# MCU.net
KiCad netlist of a schematic drawn in Altium Designer
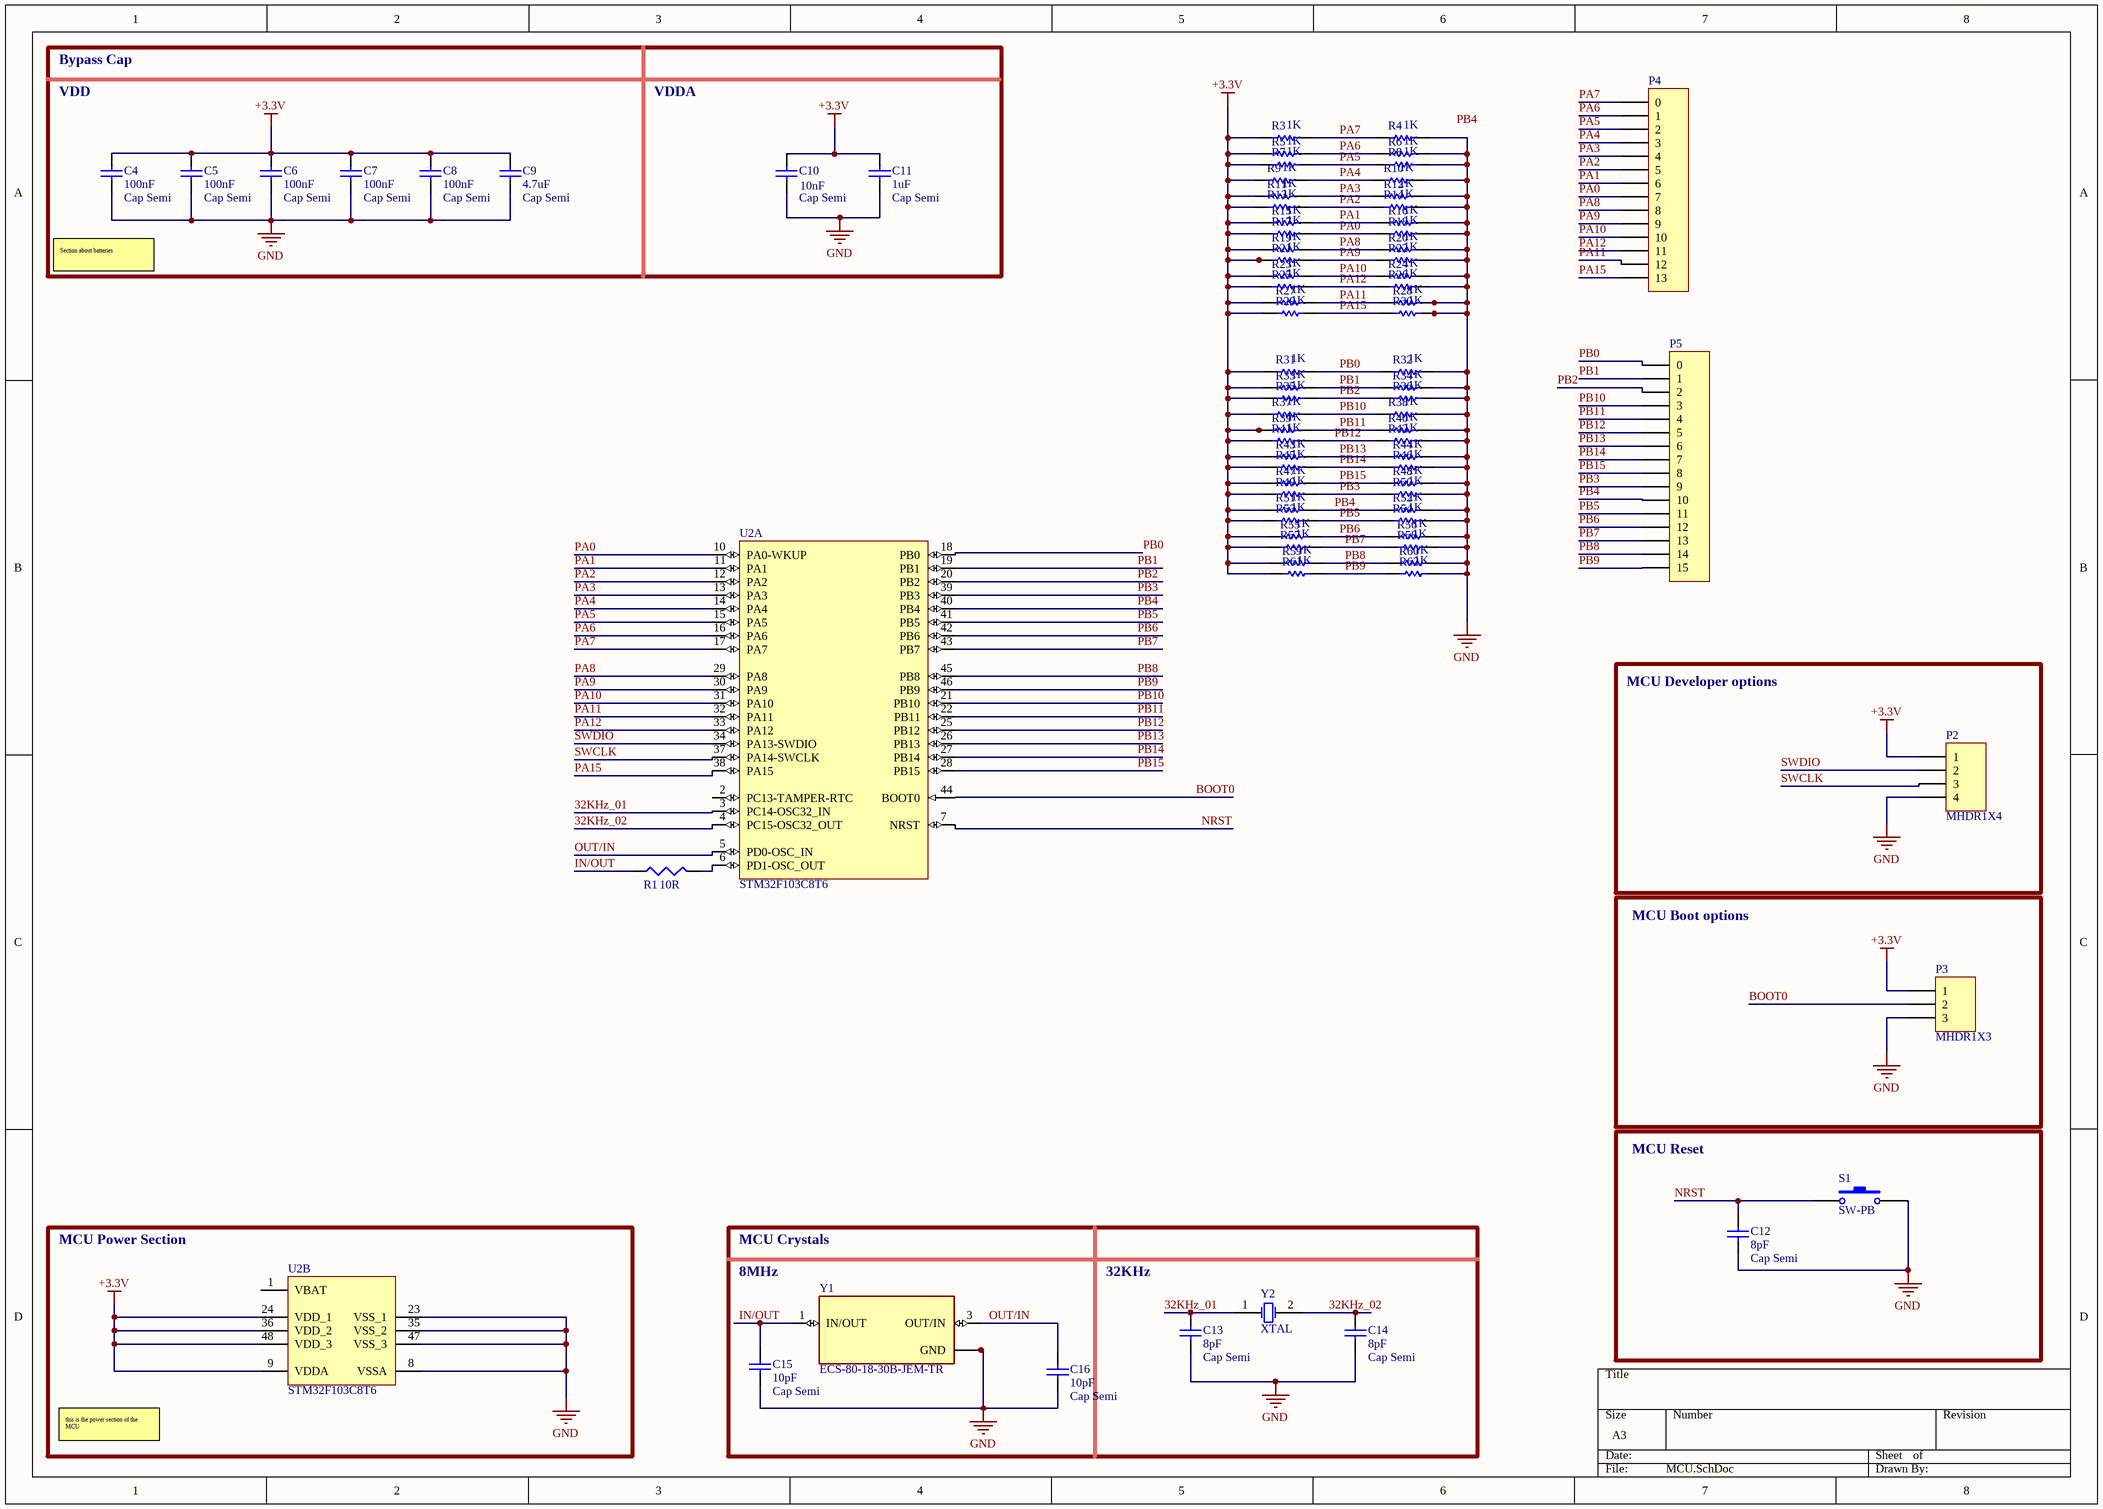
[diagram p0: MCU.SchDoc]

(export (version "E")
  (design (tool "Eeschema 10.0.6"))
  (components
    (comp (ref "C4")
      (value "Cap Semi")
      (footprint "1608[0603]")
      (description "Capacitor (Semiconductor SIM Model)")
      (fields (field (name "ALTIUM_VALUE") "100nF") (field (name "PUBLISHER") "Altium Limited"))
      (libsource (lib "Miscellaneous Devices") (part "Cap Semi"))
    )
    (comp (ref "C5")
      (value "Cap Semi")
      (footprint "1608[0603]")
      (description "Capacitor (Semiconductor SIM Model)")
      (fields (field (name "ALTIUM_VALUE") "100nF") (field (name "PUBLISHER") "Altium Limited"))
      (libsource (lib "Miscellaneous Devices") (part "Cap Semi"))
    )
    (comp (ref "C6")
      (value "Cap Semi")
      (footprint "1608[0603]")
      (description "Capacitor (Semiconductor SIM Model)")
      (fields (field (name "ALTIUM_VALUE") "100nF") (field (name "PUBLISHER") "Altium Limited"))
      (libsource (lib "Miscellaneous Devices") (part "Cap Semi"))
    )
    (comp (ref "C7")
      (value "Cap Semi")
      (footprint "1608[0603]")
      (description "Capacitor (Semiconductor SIM Model)")
      (fields (field (name "ALTIUM_VALUE") "100nF") (field (name "PUBLISHER") "Altium Limited"))
      (libsource (lib "Miscellaneous Devices") (part "Cap Semi"))
    )
    (comp (ref "C8")
      (value "Cap Semi")
      (footprint "1608[0603]")
      (description "Capacitor (Semiconductor SIM Model)")
      (fields (field (name "ALTIUM_VALUE") "100nF") (field (name "PUBLISHER") "Altium Limited"))
      (libsource (lib "Miscellaneous Devices") (part "Cap Semi"))
    )
    (comp (ref "C9")
      (value "Cap Semi")
      (footprint "1608[0603]")
      (description "Capacitor (Semiconductor SIM Model)")
      (fields (field (name "ALTIUM_VALUE") "4.7uF") (field (name "PUBLISHER") "Altium Limited"))
      (libsource (lib "Miscellaneous Devices") (part "Cap Semi"))
    )
    (comp (ref "C10")
      (value "Cap Semi")
      (footprint "1608[0603]")
      (description "Capacitor (Semiconductor SIM Model)")
      (fields (field (name "ALTIUM_VALUE") "10nF") (field (name "PUBLISHER") "Altium Limited"))
      (libsource (lib "Miscellaneous Devices") (part "Cap Semi"))
    )
    (comp (ref "C11")
      (value "Cap Semi")
      (footprint "1608[0603]")
      (description "Capacitor (Semiconductor SIM Model)")
      (fields (field (name "ALTIUM_VALUE") "1uF") (field (name "PUBLISHER") "Altium Limited"))
      (libsource (lib "Miscellaneous Devices") (part "Cap Semi"))
    )
    (comp (ref "C12")
      (value "Cap Semi")
      (footprint "0402")
      (description "Capacitor (Semiconductor SIM Model)")
      (fields (field (name "ALTIUM_VALUE") "8pF") (field (name "PUBLISHER") "Altium Limited"))
      (libsource (lib "Miscellaneous Devices") (part "Cap Semi"))
    )
    (comp (ref "C13")
      (value "Cap Semi")
      (footprint "0402")
      (description "Capacitor (Semiconductor SIM Model)")
      (fields (field (name "ALTIUM_VALUE") "8pF") (field (name "PUBLISHER") "Altium Limited"))
      (libsource (lib "Miscellaneous Devices") (part "Cap Semi"))
    )
    (comp (ref "C14")
      (value "Cap Semi")
      (footprint "0402")
      (description "Capacitor (Semiconductor SIM Model)")
      (fields (field (name "ALTIUM_VALUE") "8pF") (field (name "PUBLISHER") "Altium Limited"))
      (libsource (lib "Miscellaneous Devices") (part "Cap Semi"))
    )
    (comp (ref "C15")
      (value "Cap Semi")
      (footprint "0402")
      (description "Capacitor (Semiconductor SIM Model)")
      (fields (field (name "ALTIUM_VALUE") "10pF") (field (name "PUBLISHER") "Altium Limited"))
      (libsource (lib "Miscellaneous Devices") (part "Cap Semi"))
    )
    (comp (ref "C16")
      (value "Cap Semi")
      (footprint "0402")
      (description "Capacitor (Semiconductor SIM Model)")
      (fields (field (name "ALTIUM_VALUE") "10pF") (field (name "PUBLISHER") "Altium Limited"))
      (libsource (lib "Miscellaneous Devices") (part "Cap Semi"))
    )
    (comp (ref "P2")
      (value "MHDR1X4")
      (footprint "MHDR1X4")
      (description "Header, 4-Pin")
      (fields (field (name "PUBLISHER") "Altium Limited"))
      (libsource (lib "Miscellaneous Connectors") (part "MHDR1X4"))
    )
    (comp (ref "P3")
      (value "MHDR1X3")
      (footprint "MHDR1X3")
      (description "Header, 3-Pin")
      (fields (field (name "PUBLISHER") "Altium Limited"))
      (libsource (lib "Miscellaneous Connectors") (part "MHDR1X3"))
    )
    (comp (ref "P4")
      (value "Header 14")
      (footprint "MY_FE14")
      (description "Header, 14-Pin")
      (fields (field (name "ASID PART NUMBER") "Header 14-AS"))
      (libsource (lib "Mylib+Rev+4") (part "Header 14"))
    )
    (comp (ref "P5")
      (value "Header 16")
      (footprint "MY_FE16")
      (description "Header, 16-Pin")
      (fields (field (name "ASID PART NUMBER") "Header 16-AS"))
      (libsource (lib "Mylib+Rev+4") (part "Header 16"))
    )
    (comp (ref "R1")
      (value "10R")
      (footprint "J1-0603")
      (description "Resistor")
      (fields (field (name "Comment") "Res3") (field (name "PUBLISHER") "Altium Limited"))
      (libsource (lib "Miscellaneous Devices") (part "Res3"))
    )
    (comp (ref "R3")
      (value "1K")
      (footprint "MY_0603")
      (description "Standard resistor")
      (fields (field (name "ASID PART NUMBER") "Res-AS"))
      (libsource (lib "Mylib+Rev+4") (part "Res"))
    )
    (comp (ref "R4")
      (value "1K")
      (footprint "MY_0603")
      (description "Standard resistor")
      (fields (field (name "ASID PART NUMBER") "Res-AS"))
      (libsource (lib "Mylib+Rev+4") (part "Res"))
    )
    (comp (ref "R5")
      (value "1K")
      (footprint "MY_0603")
      (description "Standard resistor")
      (fields (field (name "ASID PART NUMBER") "Res-AS"))
      (libsource (lib "Mylib+Rev+4") (part "Res"))
    )
    (comp (ref "R6")
      (value "1K")
      (footprint "MY_0603")
      (description "Standard resistor")
      (fields (field (name "ASID PART NUMBER") "Res-AS"))
      (libsource (lib "Mylib+Rev+4") (part "Res"))
    )
    (comp (ref "R7")
      (value "1K")
      (footprint "MY_0603")
      (description "Standard resistor")
      (fields (field (name "ASID PART NUMBER") "Res-AS"))
      (libsource (lib "Mylib+Rev+4") (part "Res"))
    )
    (comp (ref "R8")
      (value "1K")
      (footprint "MY_0603")
      (description "Standard resistor")
      (fields (field (name "ASID PART NUMBER") "Res-AS"))
      (libsource (lib "Mylib+Rev+4") (part "Res"))
    )
    (comp (ref "R9")
      (value "1K")
      (footprint "MY_0603")
      (description "Standard resistor")
      (fields (field (name "ASID PART NUMBER") "Res-AS"))
      (libsource (lib "Mylib+Rev+4") (part "Res"))
    )
    (comp (ref "R10")
      (value "1K")
      (footprint "MY_0603")
      (description "Standard resistor")
      (fields (field (name "ASID PART NUMBER") "Res-AS"))
      (libsource (lib "Mylib+Rev+4") (part "Res"))
    )
    (comp (ref "R11")
      (value "1K")
      (footprint "MY_0603")
      (description "Standard resistor")
      (fields (field (name "ASID PART NUMBER") "Res-AS"))
      (libsource (lib "Mylib+Rev+4") (part "Res"))
    )
    (comp (ref "R12")
      (value "1K")
      (footprint "MY_0603")
      (description "Standard resistor")
      (fields (field (name "ASID PART NUMBER") "Res-AS"))
      (libsource (lib "Mylib+Rev+4") (part "Res"))
    )
    (comp (ref "R13")
      (value "1K")
      (footprint "MY_0603")
      (description "Standard resistor")
      (fields (field (name "ASID PART NUMBER") "Res-AS"))
      (libsource (lib "Mylib+Rev+4") (part "Res"))
    )
    (comp (ref "R14")
      (value "1K")
      (footprint "MY_0603")
      (description "Standard resistor")
      (fields (field (name "ASID PART NUMBER") "Res-AS"))
      (libsource (lib "Mylib+Rev+4") (part "Res"))
    )
    (comp (ref "R15")
      (value "1K")
      (footprint "MY_0603")
      (description "Standard resistor")
      (fields (field (name "ASID PART NUMBER") "Res-AS"))
      (libsource (lib "Mylib+Rev+4") (part "Res"))
    )
    (comp (ref "R16")
      (value "1K")
      (footprint "MY_0603")
      (description "Standard resistor")
      (fields (field (name "ASID PART NUMBER") "Res-AS"))
      (libsource (lib "Mylib+Rev+4") (part "Res"))
    )
    (comp (ref "R17")
      (value "1K")
      (footprint "MY_0603")
      (description "Standard resistor")
      (fields (field (name "ASID PART NUMBER") "Res-AS"))
      (libsource (lib "Mylib+Rev+4") (part "Res"))
    )
    (comp (ref "R18")
      (value "1K")
      (footprint "MY_0603")
      (description "Standard resistor")
      (fields (field (name "ASID PART NUMBER") "Res-AS"))
      (libsource (lib "Mylib+Rev+4") (part "Res"))
    )
    (comp (ref "R19")
      (value "1K")
      (footprint "MY_0603")
      (description "Standard resistor")
      (fields (field (name "ASID PART NUMBER") "Res-AS"))
      (libsource (lib "Mylib+Rev+4") (part "Res"))
    )
    (comp (ref "R20")
      (value "1K")
      (footprint "MY_0603")
      (description "Standard resistor")
      (fields (field (name "ASID PART NUMBER") "Res-AS"))
      (libsource (lib "Mylib+Rev+4") (part "Res"))
    )
    (comp (ref "R21")
      (value "1K")
      (footprint "MY_0603")
      (description "Standard resistor")
      (fields (field (name "ASID PART NUMBER") "Res-AS"))
      (libsource (lib "Mylib+Rev+4") (part "Res"))
    )
    (comp (ref "R22")
      (value "1K")
      (footprint "MY_0603")
      (description "Standard resistor")
      (fields (field (name "ASID PART NUMBER") "Res-AS"))
      (libsource (lib "Mylib+Rev+4") (part "Res"))
    )
    (comp (ref "R23")
      (value "1K")
      (footprint "MY_0603")
      (description "Standard resistor")
      (fields (field (name "ASID PART NUMBER") "Res-AS"))
      (libsource (lib "Mylib+Rev+4") (part "Res"))
    )
    (comp (ref "R24")
      (value "1K")
      (footprint "MY_0603")
      (description "Standard resistor")
      (fields (field (name "ASID PART NUMBER") "Res-AS"))
      (libsource (lib "Mylib+Rev+4") (part "Res"))
    )
    (comp (ref "R25")
      (value "1K")
      (footprint "MY_0603")
      (description "Standard resistor")
      (fields (field (name "ASID PART NUMBER") "Res-AS"))
      (libsource (lib "Mylib+Rev+4") (part "Res"))
    )
    (comp (ref "R26")
      (value "1K")
      (footprint "MY_0603")
      (description "Standard resistor")
      (fields (field (name "ASID PART NUMBER") "Res-AS"))
      (libsource (lib "Mylib+Rev+4") (part "Res"))
    )
    (comp (ref "R27")
      (value "1K")
      (footprint "MY_0603")
      (description "Standard resistor")
      (fields (field (name "ASID PART NUMBER") "Res-AS"))
      (libsource (lib "Mylib+Rev+4") (part "Res"))
    )
    (comp (ref "R28")
      (value "1K")
      (footprint "MY_0603")
      (description "Standard resistor")
      (fields (field (name "ASID PART NUMBER") "Res-AS"))
      (libsource (lib "Mylib+Rev+4") (part "Res"))
    )
    (comp (ref "R29")
      (value "1K")
      (footprint "MY_0603")
      (description "Standard resistor")
      (fields (field (name "ASID PART NUMBER") "Res-AS"))
      (libsource (lib "Mylib+Rev+4") (part "Res"))
    )
    (comp (ref "R30")
      (value "1K")
      (footprint "MY_0603")
      (description "Standard resistor")
      (fields (field (name "ASID PART NUMBER") "Res-AS"))
      (libsource (lib "Mylib+Rev+4") (part "Res"))
    )
    (comp (ref "R31")
      (value "1K")
      (footprint "MY_0603")
      (description "Standard resistor")
      (fields (field (name "ASID PART NUMBER") "Res-AS"))
      (libsource (lib "Mylib+Rev+4") (part "Res"))
    )
    (comp (ref "R32")
      (value "1K")
      (footprint "MY_0603")
      (description "Standard resistor")
      (fields (field (name "ASID PART NUMBER") "Res-AS"))
      (libsource (lib "Mylib+Rev+4") (part "Res"))
    )
    (comp (ref "R33")
      (value "1K")
      (footprint "MY_0603")
      (description "Standard resistor")
      (fields (field (name "ASID PART NUMBER") "Res-AS"))
      (libsource (lib "Mylib+Rev+4") (part "Res"))
    )
    (comp (ref "R34")
      (value "1K")
      (footprint "MY_0603")
      (description "Standard resistor")
      (fields (field (name "ASID PART NUMBER") "Res-AS"))
      (libsource (lib "Mylib+Rev+4") (part "Res"))
    )
    (comp (ref "R35")
      (value "1K")
      (footprint "MY_0603")
      (description "Standard resistor")
      (fields (field (name "ASID PART NUMBER") "Res-AS"))
      (libsource (lib "Mylib+Rev+4") (part "Res"))
    )
    (comp (ref "R36")
      (value "1K")
      (footprint "MY_0603")
      (description "Standard resistor")
      (fields (field (name "ASID PART NUMBER") "Res-AS"))
      (libsource (lib "Mylib+Rev+4") (part "Res"))
    )
    (comp (ref "R37")
      (value "1K")
      (footprint "MY_0603")
      (description "Standard resistor")
      (fields (field (name "ASID PART NUMBER") "Res-AS"))
      (libsource (lib "Mylib+Rev+4") (part "Res"))
    )
    (comp (ref "R38")
      (value "1K")
      (footprint "MY_0603")
      (description "Standard resistor")
      (fields (field (name "ASID PART NUMBER") "Res-AS"))
      (libsource (lib "Mylib+Rev+4") (part "Res"))
    )
    (comp (ref "R39")
      (value "1K")
      (footprint "MY_0603")
      (description "Standard resistor")
      (fields (field (name "ASID PART NUMBER") "Res-AS"))
      (libsource (lib "Mylib+Rev+4") (part "Res"))
    )
    (comp (ref "R40")
      (value "1K")
      (footprint "MY_0603")
      (description "Standard resistor")
      (fields (field (name "ASID PART NUMBER") "Res-AS"))
      (libsource (lib "Mylib+Rev+4") (part "Res"))
    )
    (comp (ref "R41")
      (value "1K")
      (footprint "MY_0603")
      (description "Standard resistor")
      (fields (field (name "ASID PART NUMBER") "Res-AS"))
      (libsource (lib "Mylib+Rev+4") (part "Res"))
    )
    (comp (ref "R42")
      (value "1K")
      (footprint "MY_0603")
      (description "Standard resistor")
      (fields (field (name "ASID PART NUMBER") "Res-AS"))
      (libsource (lib "Mylib+Rev+4") (part "Res"))
    )
    (comp (ref "R43")
      (value "1K")
      (footprint "MY_0603")
      (description "Standard resistor")
      (fields (field (name "ASID PART NUMBER") "Res-AS"))
      (libsource (lib "Mylib+Rev+4") (part "Res"))
    )
    (comp (ref "R44")
      (value "1K")
      (footprint "MY_0603")
      (description "Standard resistor")
      (fields (field (name "ASID PART NUMBER") "Res-AS"))
      (libsource (lib "Mylib+Rev+4") (part "Res"))
    )
    (comp (ref "R45")
      (value "1K")
      (footprint "MY_0603")
      (description "Standard resistor")
      (fields (field (name "ASID PART NUMBER") "Res-AS"))
      (libsource (lib "Mylib+Rev+4") (part "Res"))
    )
    (comp (ref "R46")
      (value "1K")
      (footprint "MY_0603")
      (description "Standard resistor")
      (fields (field (name "ASID PART NUMBER") "Res-AS"))
      (libsource (lib "Mylib+Rev+4") (part "Res"))
    )
    (comp (ref "R47")
      (value "1K")
      (footprint "MY_0603")
      (description "Standard resistor")
      (fields (field (name "ASID PART NUMBER") "Res-AS"))
      (libsource (lib "Mylib+Rev+4") (part "Res"))
    )
    (comp (ref "R48")
      (value "1K")
      (footprint "MY_0603")
      (description "Standard resistor")
      (fields (field (name "ASID PART NUMBER") "Res-AS"))
      (libsource (lib "Mylib+Rev+4") (part "Res"))
    )
    (comp (ref "R49")
      (value "1K")
      (footprint "MY_0603")
      (description "Standard resistor")
      (fields (field (name "ASID PART NUMBER") "Res-AS"))
      (libsource (lib "Mylib+Rev+4") (part "Res"))
    )
    (comp (ref "R50")
      (value "1K")
      (footprint "MY_0603")
      (description "Standard resistor")
      (fields (field (name "ASID PART NUMBER") "Res-AS"))
      (libsource (lib "Mylib+Rev+4") (part "Res"))
    )
    (comp (ref "R51")
      (value "1K")
      (footprint "MY_0603")
      (description "Standard resistor")
      (fields (field (name "ASID PART NUMBER") "Res-AS"))
      (libsource (lib "Mylib+Rev+4") (part "Res"))
    )
    (comp (ref "R52")
      (value "1K")
      (footprint "MY_0603")
      (description "Standard resistor")
      (fields (field (name "ASID PART NUMBER") "Res-AS"))
      (libsource (lib "Mylib+Rev+4") (part "Res"))
    )
    (comp (ref "R53")
      (value "1K")
      (footprint "MY_0603")
      (description "Standard resistor")
      (fields (field (name "ASID PART NUMBER") "Res-AS"))
      (libsource (lib "Mylib+Rev+4") (part "Res"))
    )
    (comp (ref "R54")
      (value "1K")
      (footprint "MY_0603")
      (description "Standard resistor")
      (fields (field (name "ASID PART NUMBER") "Res-AS"))
      (libsource (lib "Mylib+Rev+4") (part "Res"))
    )
    (comp (ref "R55")
      (value "1K")
      (footprint "MY_0603")
      (description "Standard resistor")
      (fields (field (name "ASID PART NUMBER") "Res-AS"))
      (libsource (lib "Mylib+Rev+4") (part "Res"))
    )
    (comp (ref "R56")
      (value "1K")
      (footprint "MY_0603")
      (description "Standard resistor")
      (fields (field (name "ASID PART NUMBER") "Res-AS"))
      (libsource (lib "Mylib+Rev+4") (part "Res"))
    )
    (comp (ref "R57")
      (value "1K")
      (footprint "MY_0603")
      (description "Standard resistor")
      (fields (field (name "ASID PART NUMBER") "Res-AS"))
      (libsource (lib "Mylib+Rev+4") (part "Res"))
    )
    (comp (ref "R58")
      (value "1K")
      (footprint "MY_0603")
      (description "Standard resistor")
      (fields (field (name "ASID PART NUMBER") "Res-AS"))
      (libsource (lib "Mylib+Rev+4") (part "Res"))
    )
    (comp (ref "R59")
      (value "1K")
      (footprint "MY_0603")
      (description "Standard resistor")
      (fields (field (name "ASID PART NUMBER") "Res-AS"))
      (libsource (lib "Mylib+Rev+4") (part "Res"))
    )
    (comp (ref "R60")
      (value "1K")
      (footprint "MY_0603")
      (description "Standard resistor")
      (fields (field (name "ASID PART NUMBER") "Res-AS"))
      (libsource (lib "Mylib+Rev+4") (part "Res"))
    )
    (comp (ref "R61")
      (value "1K")
      (footprint "MY_0603")
      (description "Standard resistor")
      (fields (field (name "ASID PART NUMBER") "Res-AS"))
      (libsource (lib "Mylib+Rev+4") (part "Res"))
    )
    (comp (ref "R62")
      (value "1K")
      (footprint "MY_0603")
      (description "Standard resistor")
      (fields (field (name "ASID PART NUMBER") "Res-AS"))
      (libsource (lib "Mylib+Rev+4") (part "Res"))
    )
    (comp (ref "S1")
      (value "SW-PB")
      (footprint "SPST-2")
      (description "Switch")
      (fields (field (name "PUBLISHER") "Altium Limited"))
      (libsource (lib "Miscellaneous Devices") (part "SW-PB"))
    )
    (comp (ref "U2")
      (value "STM32F103C8T6")
      (footprint "STM-LQFP48_N")
      (libsource (lib "STMicroelectronics STM32 F1") (part "STM32F103C8T6"))
    )
    (comp (ref "Y1")
      (value "ECS-80-18-30B-JEM-TR")
      (footprint "XTAL_ECS-80-18-30B-JEM-TR")
      (description "8 MHz Â±20ppm Crystal 18pF 100 Ohms 4-SMD, No Lead")
      (fields (field (name "MF") "ECS Inc."))
      (libsource (lib "ECS-80-18-30B-JEM-TR") (part "ECS-80-18-30B-JEM-TR"))
    )
    (comp (ref "Y2")
      (value "XTAL")
      (footprint "R38")
      (description "Crystal Oscillator")
      (fields (field (name "PUBLISHER") "Altium Limited"))
      (libsource (lib "Miscellaneous Devices") (part "XTAL"))
    )
  )
  (nets
    (net (code "1") (name "+3.3V") (class "Default")
      (node (ref "C10") (pin "2") (pinfunction "2_2") (pintype "passive"))
      (node (ref "C11") (pin "2") (pinfunction "2_2") (pintype "passive"))
      (node (ref "C4") (pin "2") (pinfunction "2_2") (pintype "passive"))
      (node (ref "C5") (pin "2") (pinfunction "2_2") (pintype "passive"))
      (node (ref "C6") (pin "2") (pinfunction "2_2") (pintype "passive"))
      (node (ref "C7") (pin "2") (pinfunction "2_2") (pintype "passive"))
      (node (ref "C8") (pin "2") (pinfunction "2_2") (pintype "passive"))
      (node (ref "C9") (pin "2") (pinfunction "2_2") (pintype "passive"))
      (node (ref "P2") (pin "1") (pinfunction "1_1") (pintype "passive"))
      (node (ref "P3") (pin "1") (pinfunction "1_1") (pintype "passive"))
      (node (ref "R11") (pin "1") (pinfunction "1_1") (pintype "passive"))
      (node (ref "R13") (pin "1") (pinfunction "1_1") (pintype "passive"))
      (node (ref "R15") (pin "1") (pinfunction "1_1") (pintype "passive"))
      (node (ref "R17") (pin "1") (pinfunction "1_1") (pintype "passive"))
      (node (ref "R19") (pin "1") (pinfunction "1_1") (pintype "passive"))
      (node (ref "R21") (pin "1") (pinfunction "1_1") (pintype "passive"))
      (node (ref "R23") (pin "1") (pinfunction "1_1") (pintype "passive"))
      (node (ref "R25") (pin "1") (pinfunction "1_1") (pintype "passive"))
      (node (ref "R27") (pin "1") (pinfunction "1_1") (pintype "passive"))
      (node (ref "R29") (pin "1") (pinfunction "1_1") (pintype "passive"))
      (node (ref "R3") (pin "1") (pinfunction "1_1") (pintype "passive"))
      (node (ref "R31") (pin "1") (pinfunction "1_1") (pintype "passive"))
      (node (ref "R33") (pin "1") (pinfunction "1_1") (pintype "passive"))
      (node (ref "R35") (pin "1") (pinfunction "1_1") (pintype "passive"))
      (node (ref "R37") (pin "1") (pinfunction "1_1") (pintype "passive"))
      (node (ref "R39") (pin "1") (pinfunction "1_1") (pintype "passive"))
      (node (ref "R41") (pin "1") (pinfunction "1_1") (pintype "passive"))
      (node (ref "R43") (pin "1") (pinfunction "1_1") (pintype "passive"))
      (node (ref "R45") (pin "1") (pinfunction "1_1") (pintype "passive"))
      (node (ref "R47") (pin "1") (pinfunction "1_1") (pintype "passive"))
      (node (ref "R49") (pin "1") (pinfunction "1_1") (pintype "passive"))
      (node (ref "R5") (pin "1") (pinfunction "1_1") (pintype "passive"))
      (node (ref "R51") (pin "1") (pinfunction "1_1") (pintype "passive"))
      (node (ref "R53") (pin "1") (pinfunction "1_1") (pintype "passive"))
      (node (ref "R55") (pin "1") (pinfunction "1_1") (pintype "passive"))
      (node (ref "R57") (pin "1") (pinfunction "1_1") (pintype "passive"))
      (node (ref "R59") (pin "1") (pinfunction "1_1") (pintype "passive"))
      (node (ref "R61") (pin "1") (pinfunction "1_1") (pintype "passive"))
      (node (ref "R7") (pin "1") (pinfunction "1_1") (pintype "passive"))
      (node (ref "R9") (pin "1") (pinfunction "1_1") (pintype "passive"))
      (node (ref "U2") (pin "24") (pinfunction "VDD_1_24") (pintype "power_in"))
      (node (ref "U2") (pin "36") (pinfunction "VDD_2_36") (pintype "power_in"))
      (node (ref "U2") (pin "48") (pinfunction "VDD_3_48") (pintype "power_in"))
      (node (ref "U2") (pin "9") (pinfunction "VDDA_9") (pintype "power_in"))
    )
    (net (code "2") (name "/32KHz_01") (class "Default")
      (node (ref "C13") (pin "2") (pinfunction "2_2") (pintype "passive"))
      (node (ref "U2") (pin "3") (pinfunction "PC14-OSC32_IN_3") (pintype "bidirectional"))
      (node (ref "Y2") (pin "1") (pinfunction "OSC1_1") (pintype "passive"))
    )
    (net (code "3") (name "/32KHz_02") (class "Default")
      (node (ref "C14") (pin "2") (pinfunction "2_2") (pintype "passive"))
      (node (ref "U2") (pin "4") (pinfunction "PC15-OSC32_OUT_4") (pintype "bidirectional"))
      (node (ref "Y2") (pin "2") (pinfunction "OSC2_2") (pintype "passive"))
    )
    (net (code "4") (name "/BOOT0") (class "Default")
      (node (ref "P3") (pin "2") (pinfunction "2_2") (pintype "passive"))
      (node (ref "U2") (pin "44") (pinfunction "BOOT0_44") (pintype "input"))
    )
    (net (code "5") (name "/IN{slash}OUT") (class "Default")
      (node (ref "C15") (pin "2") (pinfunction "2_2") (pintype "passive"))
      (node (ref "R1") (pin "1") (pinfunction "1_1") (pintype "passive"))
      (node (ref "Y1") (pin "1") (pinfunction "IN/OUT_1") (pintype "bidirectional"))
    )
    (net (code "6") (name "/NRST") (class "Default")
      (node (ref "C12") (pin "2") (pinfunction "2_2") (pintype "passive"))
      (node (ref "S1") (pin "1") (pinfunction "1_1") (pintype "passive"))
      (node (ref "U2") (pin "7") (pinfunction "NRST_7") (pintype "bidirectional"))
    )
    (net (code "7") (name "/OUT{slash}IN") (class "Default")
      (node (ref "C16") (pin "2") (pinfunction "2_2") (pintype "passive"))
      (node (ref "U2") (pin "5") (pinfunction "PD0-OSC_IN_5") (pintype "bidirectional"))
      (node (ref "Y1") (pin "3") (pinfunction "OUT/IN_3") (pintype "bidirectional"))
    )
    (net (code "8") (name "/PA0") (class "Default")
      (node (ref "P4") (pin "8") (pinfunction "7_8") (pintype "passive"))
      (node (ref "R17") (pin "2") (pinfunction "2_2") (pintype "passive"))
      (node (ref "R18") (pin "1") (pinfunction "1_1") (pintype "passive"))
      (node (ref "U2") (pin "10") (pinfunction "PA0-WKUP_10") (pintype "bidirectional"))
    )
    (net (code "9") (name "/PA1") (class "Default")
      (node (ref "P4") (pin "7") (pinfunction "6_7") (pintype "passive"))
      (node (ref "R15") (pin "2") (pinfunction "2_2") (pintype "passive"))
      (node (ref "R16") (pin "1") (pinfunction "1_1") (pintype "passive"))
      (node (ref "U2") (pin "11") (pinfunction "PA1_11") (pintype "bidirectional"))
    )
    (net (code "10") (name "/PA2") (class "Default")
      (node (ref "P4") (pin "6") (pinfunction "5_6") (pintype "passive"))
      (node (ref "R13") (pin "2") (pinfunction "2_2") (pintype "passive"))
      (node (ref "R14") (pin "1") (pinfunction "1_1") (pintype "passive"))
      (node (ref "U2") (pin "12") (pinfunction "PA2_12") (pintype "bidirectional"))
    )
    (net (code "11") (name "/PA3") (class "Default")
      (node (ref "P4") (pin "5") (pinfunction "4_5") (pintype "passive"))
      (node (ref "R11") (pin "2") (pinfunction "2_2") (pintype "passive"))
      (node (ref "R12") (pin "1") (pinfunction "1_1") (pintype "passive"))
      (node (ref "U2") (pin "13") (pinfunction "PA3_13") (pintype "bidirectional"))
    )
    (net (code "12") (name "/PA4") (class "Default")
      (node (ref "P4") (pin "4") (pinfunction "3_4") (pintype "passive"))
      (node (ref "R10") (pin "1") (pinfunction "1_1") (pintype "passive"))
      (node (ref "R9") (pin "2") (pinfunction "2_2") (pintype "passive"))
      (node (ref "U2") (pin "14") (pinfunction "PA4_14") (pintype "bidirectional"))
    )
    (net (code "13") (name "/PA5") (class "Default")
      (node (ref "P4") (pin "3") (pinfunction "2_3") (pintype "passive"))
      (node (ref "R7") (pin "2") (pinfunction "2_2") (pintype "passive"))
      (node (ref "R8") (pin "1") (pinfunction "1_1") (pintype "passive"))
      (node (ref "U2") (pin "15") (pinfunction "PA5_15") (pintype "bidirectional"))
    )
    (net (code "14") (name "/PA6") (class "Default")
      (node (ref "P4") (pin "2") (pinfunction "1_2") (pintype "passive"))
      (node (ref "R5") (pin "2") (pinfunction "2_2") (pintype "passive"))
      (node (ref "R6") (pin "1") (pinfunction "1_1") (pintype "passive"))
      (node (ref "U2") (pin "16") (pinfunction "PA6_16") (pintype "bidirectional"))
    )
    (net (code "15") (name "/PA7") (class "Default")
      (node (ref "P4") (pin "1") (pinfunction "0_1") (pintype "passive"))
      (node (ref "R3") (pin "2") (pinfunction "2_2") (pintype "passive"))
      (node (ref "R4") (pin "1") (pinfunction "1_1") (pintype "passive"))
      (node (ref "U2") (pin "17") (pinfunction "PA7_17") (pintype "bidirectional"))
    )
    (net (code "16") (name "/PA8") (class "Default")
      (node (ref "P4") (pin "9") (pinfunction "8_9") (pintype "passive"))
      (node (ref "R19") (pin "2") (pinfunction "2_2") (pintype "passive"))
      (node (ref "R20") (pin "1") (pinfunction "1_1") (pintype "passive"))
      (node (ref "U2") (pin "29") (pinfunction "PA8_29") (pintype "bidirectional"))
    )
    (net (code "17") (name "/PA9") (class "Default")
      (node (ref "P4") (pin "10") (pinfunction "9_10") (pintype "passive"))
      (node (ref "R21") (pin "2") (pinfunction "2_2") (pintype "passive"))
      (node (ref "R22") (pin "1") (pinfunction "1_1") (pintype "passive"))
      (node (ref "U2") (pin "30") (pinfunction "PA9_30") (pintype "bidirectional"))
    )
    (net (code "18") (name "/PA10") (class "Default")
      (node (ref "P4") (pin "11") (pinfunction "10_11") (pintype "passive"))
      (node (ref "R23") (pin "2") (pinfunction "2_2") (pintype "passive"))
      (node (ref "R24") (pin "1") (pinfunction "1_1") (pintype "passive"))
      (node (ref "U2") (pin "31") (pinfunction "PA10_31") (pintype "bidirectional"))
    )
    (net (code "19") (name "/PA11") (class "Default")
      (node (ref "P4") (pin "13") (pinfunction "12_13") (pintype "passive"))
      (node (ref "R27") (pin "2") (pinfunction "2_2") (pintype "passive"))
      (node (ref "R28") (pin "1") (pinfunction "1_1") (pintype "passive"))
      (node (ref "U2") (pin "32") (pinfunction "PA11_32") (pintype "bidirectional"))
    )
    (net (code "20") (name "/PA12") (class "Default")
      (node (ref "P4") (pin "12") (pinfunction "11_12") (pintype "passive"))
      (node (ref "R25") (pin "2") (pinfunction "2_2") (pintype "passive"))
      (node (ref "R26") (pin "1") (pinfunction "1_1") (pintype "passive"))
      (node (ref "U2") (pin "33") (pinfunction "PA12_33") (pintype "bidirectional"))
    )
    (net (code "21") (name "/PA15") (class "Default")
      (node (ref "P4") (pin "14") (pinfunction "13_14") (pintype "passive"))
      (node (ref "R29") (pin "2") (pinfunction "2_2") (pintype "passive"))
      (node (ref "R30") (pin "1") (pinfunction "1_1") (pintype "passive"))
      (node (ref "U2") (pin "38") (pinfunction "PA15_38") (pintype "bidirectional"))
    )
    (net (code "22") (name "/PB0") (class "Default")
      (node (ref "P5") (pin "1") (pinfunction "0_1") (pintype "passive"))
      (node (ref "R31") (pin "2") (pinfunction "2_2") (pintype "passive"))
      (node (ref "R32") (pin "1") (pinfunction "1_1") (pintype "passive"))
      (node (ref "U2") (pin "18") (pinfunction "PB0_18") (pintype "bidirectional"))
    )
    (net (code "23") (name "/PB1") (class "Default")
      (node (ref "P5") (pin "2") (pinfunction "1_2") (pintype "passive"))
      (node (ref "R33") (pin "2") (pinfunction "2_2") (pintype "passive"))
      (node (ref "R34") (pin "1") (pinfunction "1_1") (pintype "passive"))
      (node (ref "U2") (pin "19") (pinfunction "PB1_19") (pintype "bidirectional"))
    )
    (net (code "24") (name "/PB2") (class "Default")
      (node (ref "P5") (pin "3") (pinfunction "2_3") (pintype "passive"))
      (node (ref "R35") (pin "2") (pinfunction "2_2") (pintype "passive"))
      (node (ref "R36") (pin "1") (pinfunction "1_1") (pintype "passive"))
      (node (ref "U2") (pin "20") (pinfunction "PB2_20") (pintype "bidirectional"))
    )
    (net (code "25") (name "/PB3") (class "Default")
      (node (ref "P5") (pin "10") (pinfunction "9_10") (pintype "passive"))
      (node (ref "R49") (pin "2") (pinfunction "2_2") (pintype "passive"))
      (node (ref "R50") (pin "1") (pinfunction "1_1") (pintype "passive"))
      (node (ref "U2") (pin "39") (pinfunction "PB3_39") (pintype "bidirectional"))
    )
    (net (code "26") (name "/PB4") (class "Default")
      (node (ref "P5") (pin "11") (pinfunction "10_11") (pintype "passive"))
      (node (ref "R51") (pin "2") (pinfunction "2_2") (pintype "passive"))
      (node (ref "R52") (pin "1") (pinfunction "1_1") (pintype "passive"))
      (node (ref "U2") (pin "40") (pinfunction "PB4_40") (pintype "bidirectional"))
    )
    (net (code "27") (name "/PB5") (class "Default")
      (node (ref "P5") (pin "12") (pinfunction "11_12") (pintype "passive"))
      (node (ref "R53") (pin "2") (pinfunction "2_2") (pintype "passive"))
      (node (ref "R54") (pin "1") (pinfunction "1_1") (pintype "passive"))
      (node (ref "U2") (pin "41") (pinfunction "PB5_41") (pintype "bidirectional"))
    )
    (net (code "28") (name "/PB6") (class "Default")
      (node (ref "P5") (pin "13") (pinfunction "12_13") (pintype "passive"))
      (node (ref "R55") (pin "2") (pinfunction "2_2") (pintype "passive"))
      (node (ref "R56") (pin "1") (pinfunction "1_1") (pintype "passive"))
      (node (ref "U2") (pin "42") (pinfunction "PB6_42") (pintype "bidirectional"))
    )
    (net (code "29") (name "/PB7") (class "Default")
      (node (ref "P5") (pin "14") (pinfunction "13_14") (pintype "passive"))
      (node (ref "R57") (pin "2") (pinfunction "2_2") (pintype "passive"))
      (node (ref "R58") (pin "1") (pinfunction "1_1") (pintype "passive"))
      (node (ref "U2") (pin "43") (pinfunction "PB7_43") (pintype "bidirectional"))
    )
    (net (code "30") (name "/PB8") (class "Default")
      (node (ref "P5") (pin "15") (pinfunction "14_15") (pintype "passive"))
      (node (ref "R59") (pin "2") (pinfunction "2_2") (pintype "passive"))
      (node (ref "R60") (pin "1") (pinfunction "1_1") (pintype "passive"))
      (node (ref "U2") (pin "45") (pinfunction "PB8_45") (pintype "bidirectional"))
    )
    (net (code "31") (name "/PB9") (class "Default")
      (node (ref "P5") (pin "16") (pinfunction "15_16") (pintype "passive"))
      (node (ref "R61") (pin "2") (pinfunction "2_2") (pintype "passive"))
      (node (ref "R62") (pin "1") (pinfunction "1_1") (pintype "passive"))
      (node (ref "U2") (pin "46") (pinfunction "PB9_46") (pintype "bidirectional"))
    )
    (net (code "32") (name "/PB10") (class "Default")
      (node (ref "P5") (pin "4") (pinfunction "3_4") (pintype "passive"))
      (node (ref "R37") (pin "2") (pinfunction "2_2") (pintype "passive"))
      (node (ref "R38") (pin "1") (pinfunction "1_1") (pintype "passive"))
      (node (ref "U2") (pin "21") (pinfunction "PB10_21") (pintype "bidirectional"))
    )
    (net (code "33") (name "/PB11") (class "Default")
      (node (ref "P5") (pin "5") (pinfunction "4_5") (pintype "passive"))
      (node (ref "R39") (pin "2") (pinfunction "2_2") (pintype "passive"))
      (node (ref "R40") (pin "1") (pinfunction "1_1") (pintype "passive"))
      (node (ref "U2") (pin "22") (pinfunction "PB11_22") (pintype "bidirectional"))
    )
    (net (code "34") (name "/PB12") (class "Default")
      (node (ref "P5") (pin "6") (pinfunction "5_6") (pintype "passive"))
      (node (ref "R41") (pin "2") (pinfunction "2_2") (pintype "passive"))
      (node (ref "R42") (pin "1") (pinfunction "1_1") (pintype "passive"))
      (node (ref "U2") (pin "25") (pinfunction "PB12_25") (pintype "bidirectional"))
    )
    (net (code "35") (name "/PB13") (class "Default")
      (node (ref "P5") (pin "7") (pinfunction "6_7") (pintype "passive"))
      (node (ref "R43") (pin "2") (pinfunction "2_2") (pintype "passive"))
      (node (ref "R44") (pin "1") (pinfunction "1_1") (pintype "passive"))
      (node (ref "U2") (pin "26") (pinfunction "PB13_26") (pintype "bidirectional"))
    )
    (net (code "36") (name "/PB14") (class "Default")
      (node (ref "P5") (pin "8") (pinfunction "7_8") (pintype "passive"))
      (node (ref "R45") (pin "2") (pinfunction "2_2") (pintype "passive"))
      (node (ref "R46") (pin "1") (pinfunction "1_1") (pintype "passive"))
      (node (ref "U2") (pin "27") (pinfunction "PB14_27") (pintype "bidirectional"))
    )
    (net (code "37") (name "/PB15") (class "Default")
      (node (ref "P5") (pin "9") (pinfunction "8_9") (pintype "passive"))
      (node (ref "R47") (pin "2") (pinfunction "2_2") (pintype "passive"))
      (node (ref "R48") (pin "1") (pinfunction "1_1") (pintype "passive"))
      (node (ref "U2") (pin "28") (pinfunction "PB15_28") (pintype "bidirectional"))
    )
    (net (code "38") (name "/SWCLK") (class "Default")
      (node (ref "P2") (pin "3") (pinfunction "3_3") (pintype "passive"))
      (node (ref "U2") (pin "37") (pinfunction "PA14-SWCLK_37") (pintype "bidirectional"))
    )
    (net (code "39") (name "/SWDIO") (class "Default")
      (node (ref "P2") (pin "2") (pinfunction "2_2") (pintype "passive"))
      (node (ref "U2") (pin "34") (pinfunction "PA13-SWDIO_34") (pintype "bidirectional"))
    )
    (net (code "40") (name "GND") (class "Default")
      (node (ref "C10") (pin "1") (pinfunction "1_1") (pintype "passive"))
      (node (ref "C11") (pin "1") (pinfunction "1_1") (pintype "passive"))
      (node (ref "C12") (pin "1") (pinfunction "1_1") (pintype "passive"))
      (node (ref "C13") (pin "1") (pinfunction "1_1") (pintype "passive"))
      (node (ref "C14") (pin "1") (pinfunction "1_1") (pintype "passive"))
      (node (ref "C15") (pin "1") (pinfunction "1_1") (pintype "passive"))
      (node (ref "C16") (pin "1") (pinfunction "1_1") (pintype "passive"))
      (node (ref "C4") (pin "1") (pinfunction "1_1") (pintype "passive"))
      (node (ref "C5") (pin "1") (pinfunction "1_1") (pintype "passive"))
      (node (ref "C6") (pin "1") (pinfunction "1_1") (pintype "passive"))
      (node (ref "C7") (pin "1") (pinfunction "1_1") (pintype "passive"))
      (node (ref "C8") (pin "1") (pinfunction "1_1") (pintype "passive"))
      (node (ref "C9") (pin "1") (pinfunction "1_1") (pintype "passive"))
      (node (ref "P2") (pin "4") (pinfunction "4_4") (pintype "passive"))
      (node (ref "P3") (pin "3") (pinfunction "3_3") (pintype "passive"))
      (node (ref "R10") (pin "2") (pinfunction "2_2") (pintype "passive"))
      (node (ref "R12") (pin "2") (pinfunction "2_2") (pintype "passive"))
      (node (ref "R14") (pin "2") (pinfunction "2_2") (pintype "passive"))
      (node (ref "R16") (pin "2") (pinfunction "2_2") (pintype "passive"))
      (node (ref "R18") (pin "2") (pinfunction "2_2") (pintype "passive"))
      (node (ref "R20") (pin "2") (pinfunction "2_2") (pintype "passive"))
      (node (ref "R22") (pin "2") (pinfunction "2_2") (pintype "passive"))
      (node (ref "R24") (pin "2") (pinfunction "2_2") (pintype "passive"))
      (node (ref "R26") (pin "2") (pinfunction "2_2") (pintype "passive"))
      (node (ref "R28") (pin "2") (pinfunction "2_2") (pintype "passive"))
      (node (ref "R30") (pin "2") (pinfunction "2_2") (pintype "passive"))
      (node (ref "R32") (pin "2") (pinfunction "2_2") (pintype "passive"))
      (node (ref "R34") (pin "2") (pinfunction "2_2") (pintype "passive"))
      (node (ref "R36") (pin "2") (pinfunction "2_2") (pintype "passive"))
      (node (ref "R38") (pin "2") (pinfunction "2_2") (pintype "passive"))
      (node (ref "R4") (pin "2") (pinfunction "2_2") (pintype "passive"))
      (node (ref "R40") (pin "2") (pinfunction "2_2") (pintype "passive"))
      (node (ref "R42") (pin "2") (pinfunction "2_2") (pintype "passive"))
      (node (ref "R44") (pin "2") (pinfunction "2_2") (pintype "passive"))
      (node (ref "R46") (pin "2") (pinfunction "2_2") (pintype "passive"))
      (node (ref "R48") (pin "2") (pinfunction "2_2") (pintype "passive"))
      (node (ref "R50") (pin "2") (pinfunction "2_2") (pintype "passive"))
      (node (ref "R52") (pin "2") (pinfunction "2_2") (pintype "passive"))
      (node (ref "R54") (pin "2") (pinfunction "2_2") (pintype "passive"))
      (node (ref "R56") (pin "2") (pinfunction "2_2") (pintype "passive"))
      (node (ref "R58") (pin "2") (pinfunction "2_2") (pintype "passive"))
      (node (ref "R6") (pin "2") (pinfunction "2_2") (pintype "passive"))
      (node (ref "R60") (pin "2") (pinfunction "2_2") (pintype "passive"))
      (node (ref "R62") (pin "2") (pinfunction "2_2") (pintype "passive"))
      (node (ref "R8") (pin "2") (pinfunction "2_2") (pintype "passive"))
      (node (ref "S1") (pin "2") (pinfunction "2_2") (pintype "passive"))
      (node (ref "U2") (pin "23") (pinfunction "VSS_1_23") (pintype "power_in"))
      (node (ref "U2") (pin "35") (pinfunction "VSS_2_35") (pintype "power_in"))
      (node (ref "U2") (pin "47") (pinfunction "VSS_3_47") (pintype "power_in"))
      (node (ref "U2") (pin "8") (pinfunction "VSSA_8") (pintype "power_in"))
      (node (ref "Y1") (pin "2") (pinfunction "GND_2") (pintype "power_in"))
      (node (ref "Y1") (pin "4") (pinfunction "GND_4") (pintype "power_in"))
    )
    (net (code "41") (name "Net-(U2A-PD1-OSC_OUT)") (class "Default")
      (node (ref "R1") (pin "2") (pinfunction "2_2") (pintype "passive"))
      (node (ref "U2") (pin "6") (pinfunction "PD1-OSC_OUT_6") (pintype "bidirectional"))
    )
    (net (code "42") (name "unconnected-(U2A-PC13-TAMPER-RTC-Pad2)") (class "Default")
      (node (ref "U2") (pin "2") (pinfunction "PC13-TAMPER-RTC_2") (pintype "bidirectional"))
    )
    (net (code "43") (name "unconnected-(U2B-VBAT-Pad1)") (class "Default")
      (node (ref "U2") (pin "1") (pinfunction "VBAT_1") (pintype "power_in"))
    )
  )
)
